# pc_fdc1004_brk.net
KiCad netlist of a schematic drawn in EAGLE
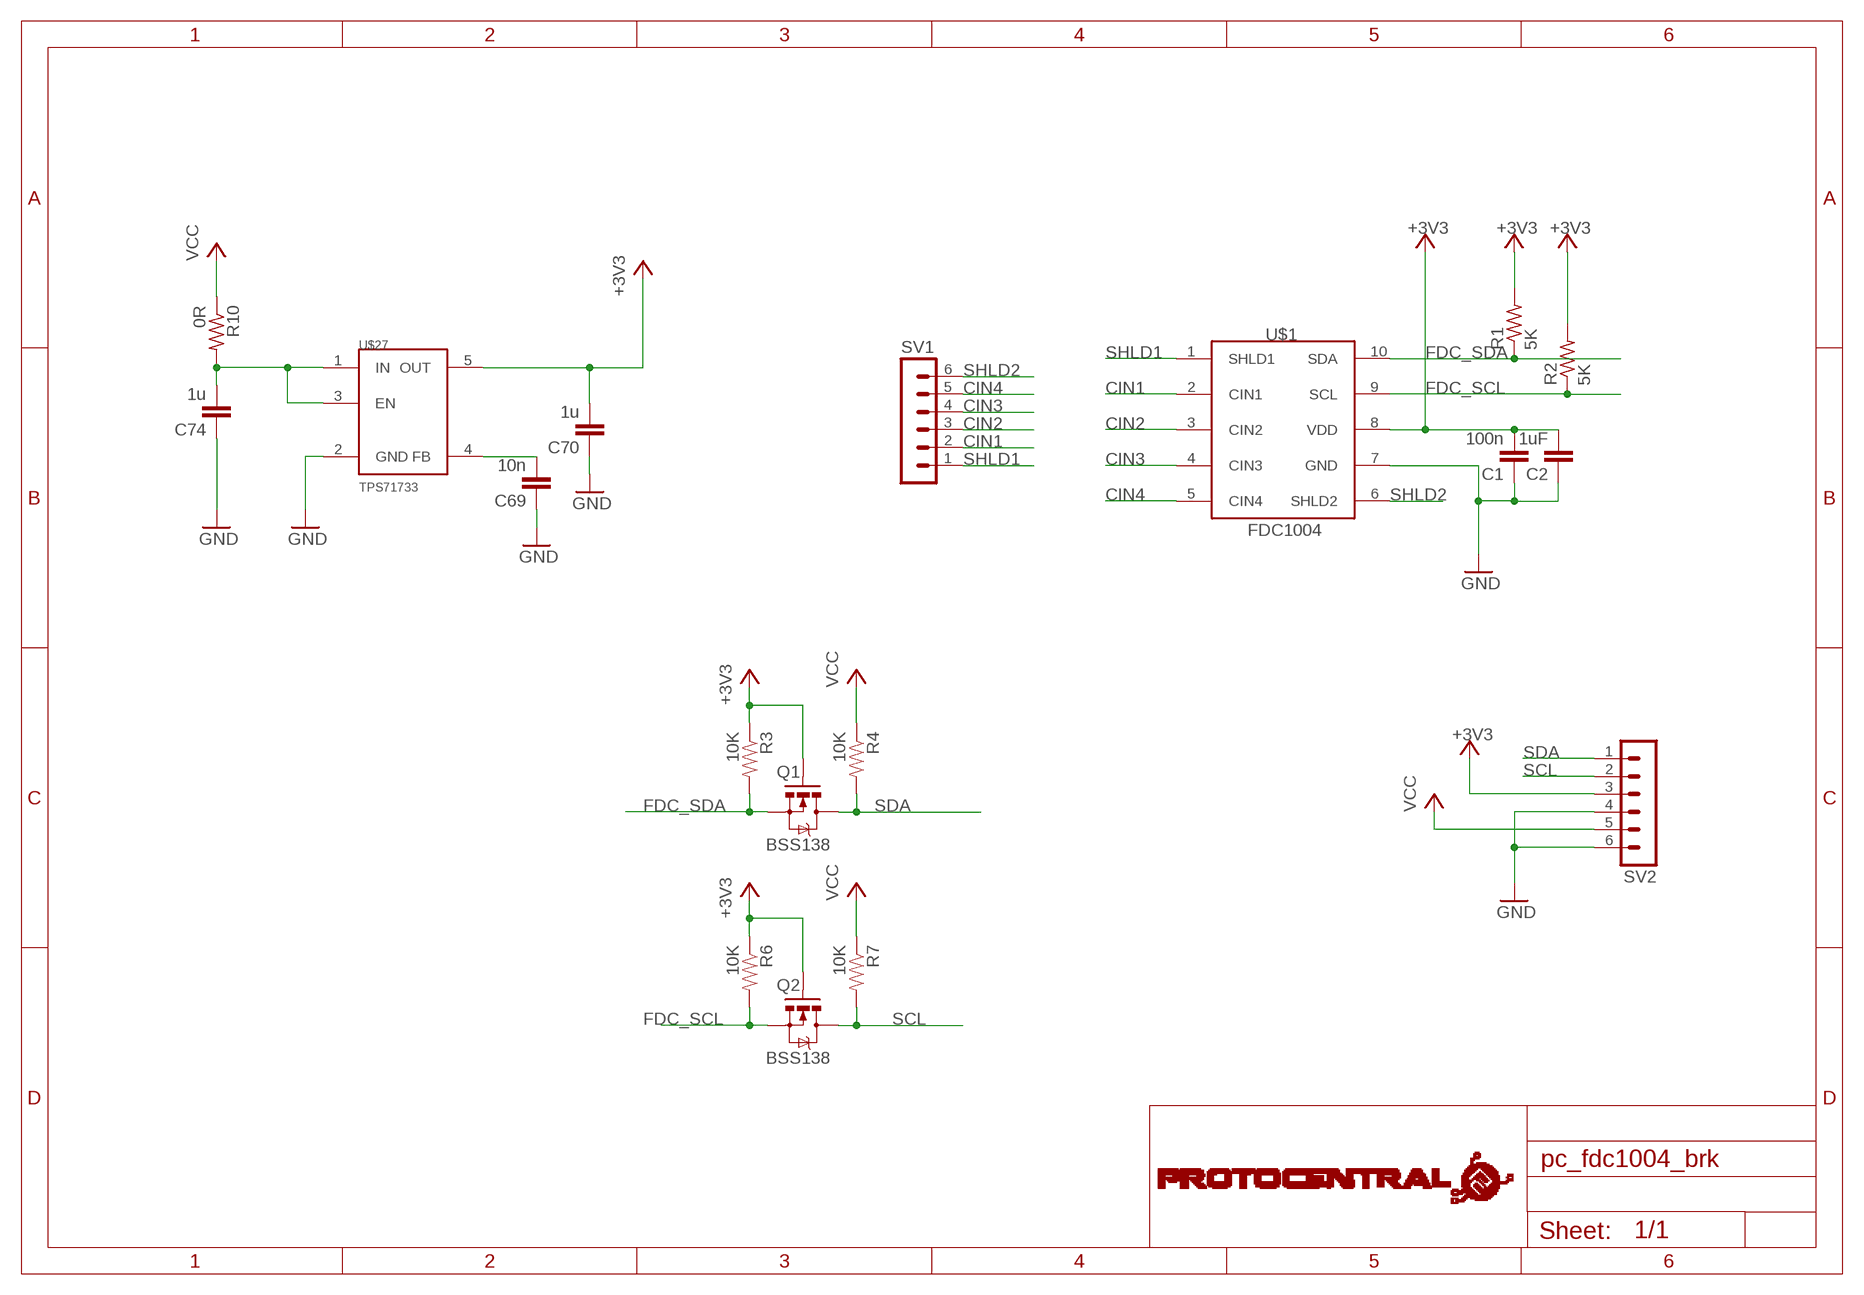
[diagram p0: schematic, sheet 1]

(export (version "E")
  (design (tool "Eeschema 10.0.6"))
  (components
    (comp (ref "C1")
      (value "100n")
      (footprint "eagle-import:C0805")
      (libsource (lib "eagle-import") (part "C-EUC0805"))
    )
    (comp (ref "C2")
      (value "1uF")
      (footprint "eagle-import:C0805")
      (libsource (lib "eagle-import") (part "C-EUC0805"))
    )
    (comp (ref "C69")
      (value "10n")
      (footprint "eagle-import:C0805")
      (libsource (lib "eagle-import") (part "C-EUC0805"))
    )
    (comp (ref "C70")
      (value "1u")
      (footprint "eagle-import:C0805")
      (libsource (lib "eagle-import") (part "C-EUC0805"))
    )
    (comp (ref "C74")
      (value "1u")
      (footprint "eagle-import:C0805")
      (libsource (lib "eagle-import") (part "C-EUC0805"))
    )
    (comp (ref "Q1")
      (value "BSS138")
      (footprint "eagle-import:SOT23-3")
      (libsource (lib "eagle-import") (part "MOSFET-NCHANNELSMD"))
    )
    (comp (ref "Q2")
      (value "BSS138")
      (footprint "eagle-import:SOT23-3")
      (libsource (lib "eagle-import") (part "MOSFET-NCHANNELSMD"))
    )
    (comp (ref "R1")
      (value "5K")
      (footprint "eagle-import:R0805")
      (libsource (lib "eagle-import") (part "R-US_R0805"))
    )
    (comp (ref "R2")
      (value "5K")
      (footprint "eagle-import:R0805")
      (libsource (lib "eagle-import") (part "R-US_R0805"))
    )
    (comp (ref "R3")
      (value "10K")
      (footprint "eagle-import:0603-RES")
      (libsource (lib "eagle-import") (part "RESISTOR0603-RES"))
    )
    (comp (ref "R4")
      (value "10K")
      (footprint "eagle-import:0603-RES")
      (libsource (lib "eagle-import") (part "RESISTOR0603-RES"))
    )
    (comp (ref "R6")
      (value "10K")
      (footprint "eagle-import:0603-RES")
      (libsource (lib "eagle-import") (part "RESISTOR0603-RES"))
    )
    (comp (ref "R7")
      (value "10K")
      (footprint "eagle-import:0603-RES")
      (libsource (lib "eagle-import") (part "RESISTOR0603-RES"))
    )
    (comp (ref "R10")
      (value "0R")
      (footprint "eagle-import:R0805")
      (libsource (lib "eagle-import") (part "R-US_R0805"))
    )
    (comp (ref "SV1")
      (value "MA06-1")
      (footprint "eagle-import:MA06-1")
      (libsource (lib "eagle-import") (part "MA06-1"))
    )
    (comp (ref "SV2")
      (value "MA06-1")
      (footprint "eagle-import:MA06-1")
      (libsource (lib "eagle-import") (part "MA06-1"))
    )
    (comp (ref "U$1")
      (value "FDC1004")
      (footprint "eagle-import:VSSOP-10")
      (libsource (lib "eagle-import") (part "FDC1004"))
    )
    (comp (ref "U$6")
      (value "PROTY_LOGO_WITH_TEXT")
      (footprint "eagle-import:PROTY_WITH_TEXT")
      (libsource (lib "eagle-import") (part "PROTY_LOGO_WITH_TEXT"))
    )
    (comp (ref "U$27")
      (value "TPS71733")
      (footprint "eagle-import:SC70-5")
      (libsource (lib "eagle-import") (part "TPS717XX"))
    )
  )
  (nets
    (net (code "1") (name "+3V3") (class "Default")
      (node (ref "C1") (pin "2") (pinfunction "2_2") (pintype "passive"))
      (node (ref "C2") (pin "2") (pinfunction "2_2") (pintype "passive"))
      (node (ref "C70") (pin "2") (pinfunction "2_2") (pintype "passive"))
      (node (ref "Q1") (pin "1") (pinfunction "G_1") (pintype "passive"))
      (node (ref "Q2") (pin "1") (pinfunction "G_1") (pintype "passive"))
      (node (ref "R1") (pin "2") (pinfunction "2_2") (pintype "passive"))
      (node (ref "R2") (pin "2") (pinfunction "2_2") (pintype "passive"))
      (node (ref "R3") (pin "1") (pinfunction "1_1") (pintype "passive"))
      (node (ref "R6") (pin "1") (pinfunction "1_1") (pintype "passive"))
      (node (ref "SV2") (pin "3") (pinfunction "3_3") (pintype "passive"))
      (node (ref "U$1") (pin "8") (pinfunction "VDD_8") (pintype "bidirectional"))
      (node (ref "U$27") (pin "5") (pinfunction "OUT_5") (pintype "bidirectional"))
    )
    (net (code "2") (name "/CIN1") (class "Default")
      (node (ref "SV1") (pin "2") (pinfunction "2_2") (pintype "passive"))
      (node (ref "U$1") (pin "2") (pinfunction "CIN1_2") (pintype "bidirectional"))
    )
    (net (code "3") (name "/CIN2") (class "Default")
      (node (ref "SV1") (pin "3") (pinfunction "3_3") (pintype "passive"))
      (node (ref "U$1") (pin "3") (pinfunction "CIN2_3") (pintype "bidirectional"))
    )
    (net (code "4") (name "/CIN3") (class "Default")
      (node (ref "SV1") (pin "4") (pinfunction "4_4") (pintype "passive"))
      (node (ref "U$1") (pin "4") (pinfunction "CIN3_4") (pintype "bidirectional"))
    )
    (net (code "5") (name "/CIN4") (class "Default")
      (node (ref "SV1") (pin "5") (pinfunction "5_5") (pintype "passive"))
      (node (ref "U$1") (pin "5") (pinfunction "CIN4_5") (pintype "bidirectional"))
    )
    (net (code "6") (name "/FDC_SCL") (class "Default")
      (node (ref "Q2") (pin "2") (pinfunction "S_2") (pintype "passive"))
      (node (ref "R2") (pin "1") (pinfunction "1_1") (pintype "passive"))
      (node (ref "R6") (pin "2") (pinfunction "2_2") (pintype "passive"))
      (node (ref "U$1") (pin "9") (pinfunction "SCL_9") (pintype "bidirectional"))
    )
    (net (code "7") (name "/FDC_SDA") (class "Default")
      (node (ref "Q1") (pin "2") (pinfunction "S_2") (pintype "passive"))
      (node (ref "R1") (pin "1") (pinfunction "1_1") (pintype "passive"))
      (node (ref "R3") (pin "2") (pinfunction "2_2") (pintype "passive"))
      (node (ref "U$1") (pin "10") (pinfunction "SDA_10") (pintype "bidirectional"))
    )
    (net (code "8") (name "/SCL") (class "Default")
      (node (ref "Q2") (pin "3") (pinfunction "D_3") (pintype "passive"))
      (node (ref "R7") (pin "2") (pinfunction "2_2") (pintype "passive"))
      (node (ref "SV2") (pin "2") (pinfunction "2_2") (pintype "passive"))
    )
    (net (code "9") (name "/SDA") (class "Default")
      (node (ref "Q1") (pin "3") (pinfunction "D_3") (pintype "passive"))
      (node (ref "R4") (pin "2") (pinfunction "2_2") (pintype "passive"))
      (node (ref "SV2") (pin "1") (pinfunction "1_1") (pintype "passive"))
    )
    (net (code "10") (name "/SHLD1") (class "Default")
      (node (ref "SV1") (pin "1") (pinfunction "1_1") (pintype "passive"))
      (node (ref "U$1") (pin "1") (pinfunction "SHLD1_1") (pintype "bidirectional"))
    )
    (net (code "11") (name "/SHLD2") (class "Default")
      (node (ref "SV1") (pin "6") (pinfunction "6_6") (pintype "passive"))
      (node (ref "U$1") (pin "6") (pinfunction "SHLD2_6") (pintype "bidirectional"))
    )
    (net (code "12") (name "GND") (class "Default")
      (node (ref "C1") (pin "1") (pinfunction "1_1") (pintype "passive"))
      (node (ref "C2") (pin "1") (pinfunction "1_1") (pintype "passive"))
      (node (ref "C69") (pin "1") (pinfunction "1_1") (pintype "passive"))
      (node (ref "C70") (pin "1") (pinfunction "1_1") (pintype "passive"))
      (node (ref "C74") (pin "1") (pinfunction "1_1") (pintype "passive"))
      (node (ref "SV2") (pin "4") (pinfunction "4_4") (pintype "passive"))
      (node (ref "SV2") (pin "6") (pinfunction "6_6") (pintype "passive"))
      (node (ref "U$1") (pin "7") (pinfunction "GND_7") (pintype "bidirectional"))
      (node (ref "U$27") (pin "2") (pinfunction "GND_2") (pintype "bidirectional"))
    )
    (net (code "13") (name "Net-(U$27-EN)") (class "Default")
      (node (ref "C74") (pin "2") (pinfunction "2_2") (pintype "passive"))
      (node (ref "R10") (pin "2") (pinfunction "2_2") (pintype "passive"))
      (node (ref "U$27") (pin "1") (pinfunction "IN_1") (pintype "bidirectional"))
      (node (ref "U$27") (pin "3") (pinfunction "EN_3") (pintype "bidirectional"))
    )
    (net (code "14") (name "Net-(U$27-FB)") (class "Default")
      (node (ref "C69") (pin "2") (pinfunction "2_2") (pintype "passive"))
      (node (ref "U$27") (pin "4") (pinfunction "FB_4") (pintype "bidirectional"))
    )
    (net (code "15") (name "VCC") (class "Default")
      (node (ref "R10") (pin "1") (pinfunction "1_1") (pintype "passive"))
      (node (ref "R4") (pin "1") (pinfunction "1_1") (pintype "passive"))
      (node (ref "R7") (pin "1") (pinfunction "1_1") (pintype "passive"))
      (node (ref "SV2") (pin "5") (pinfunction "5_5") (pintype "passive"))
    )
  )
)
